# SAM_E54_Xplained_Pro_current_measurement.net
KiCad netlist of a schematic drawn in Altium Designer
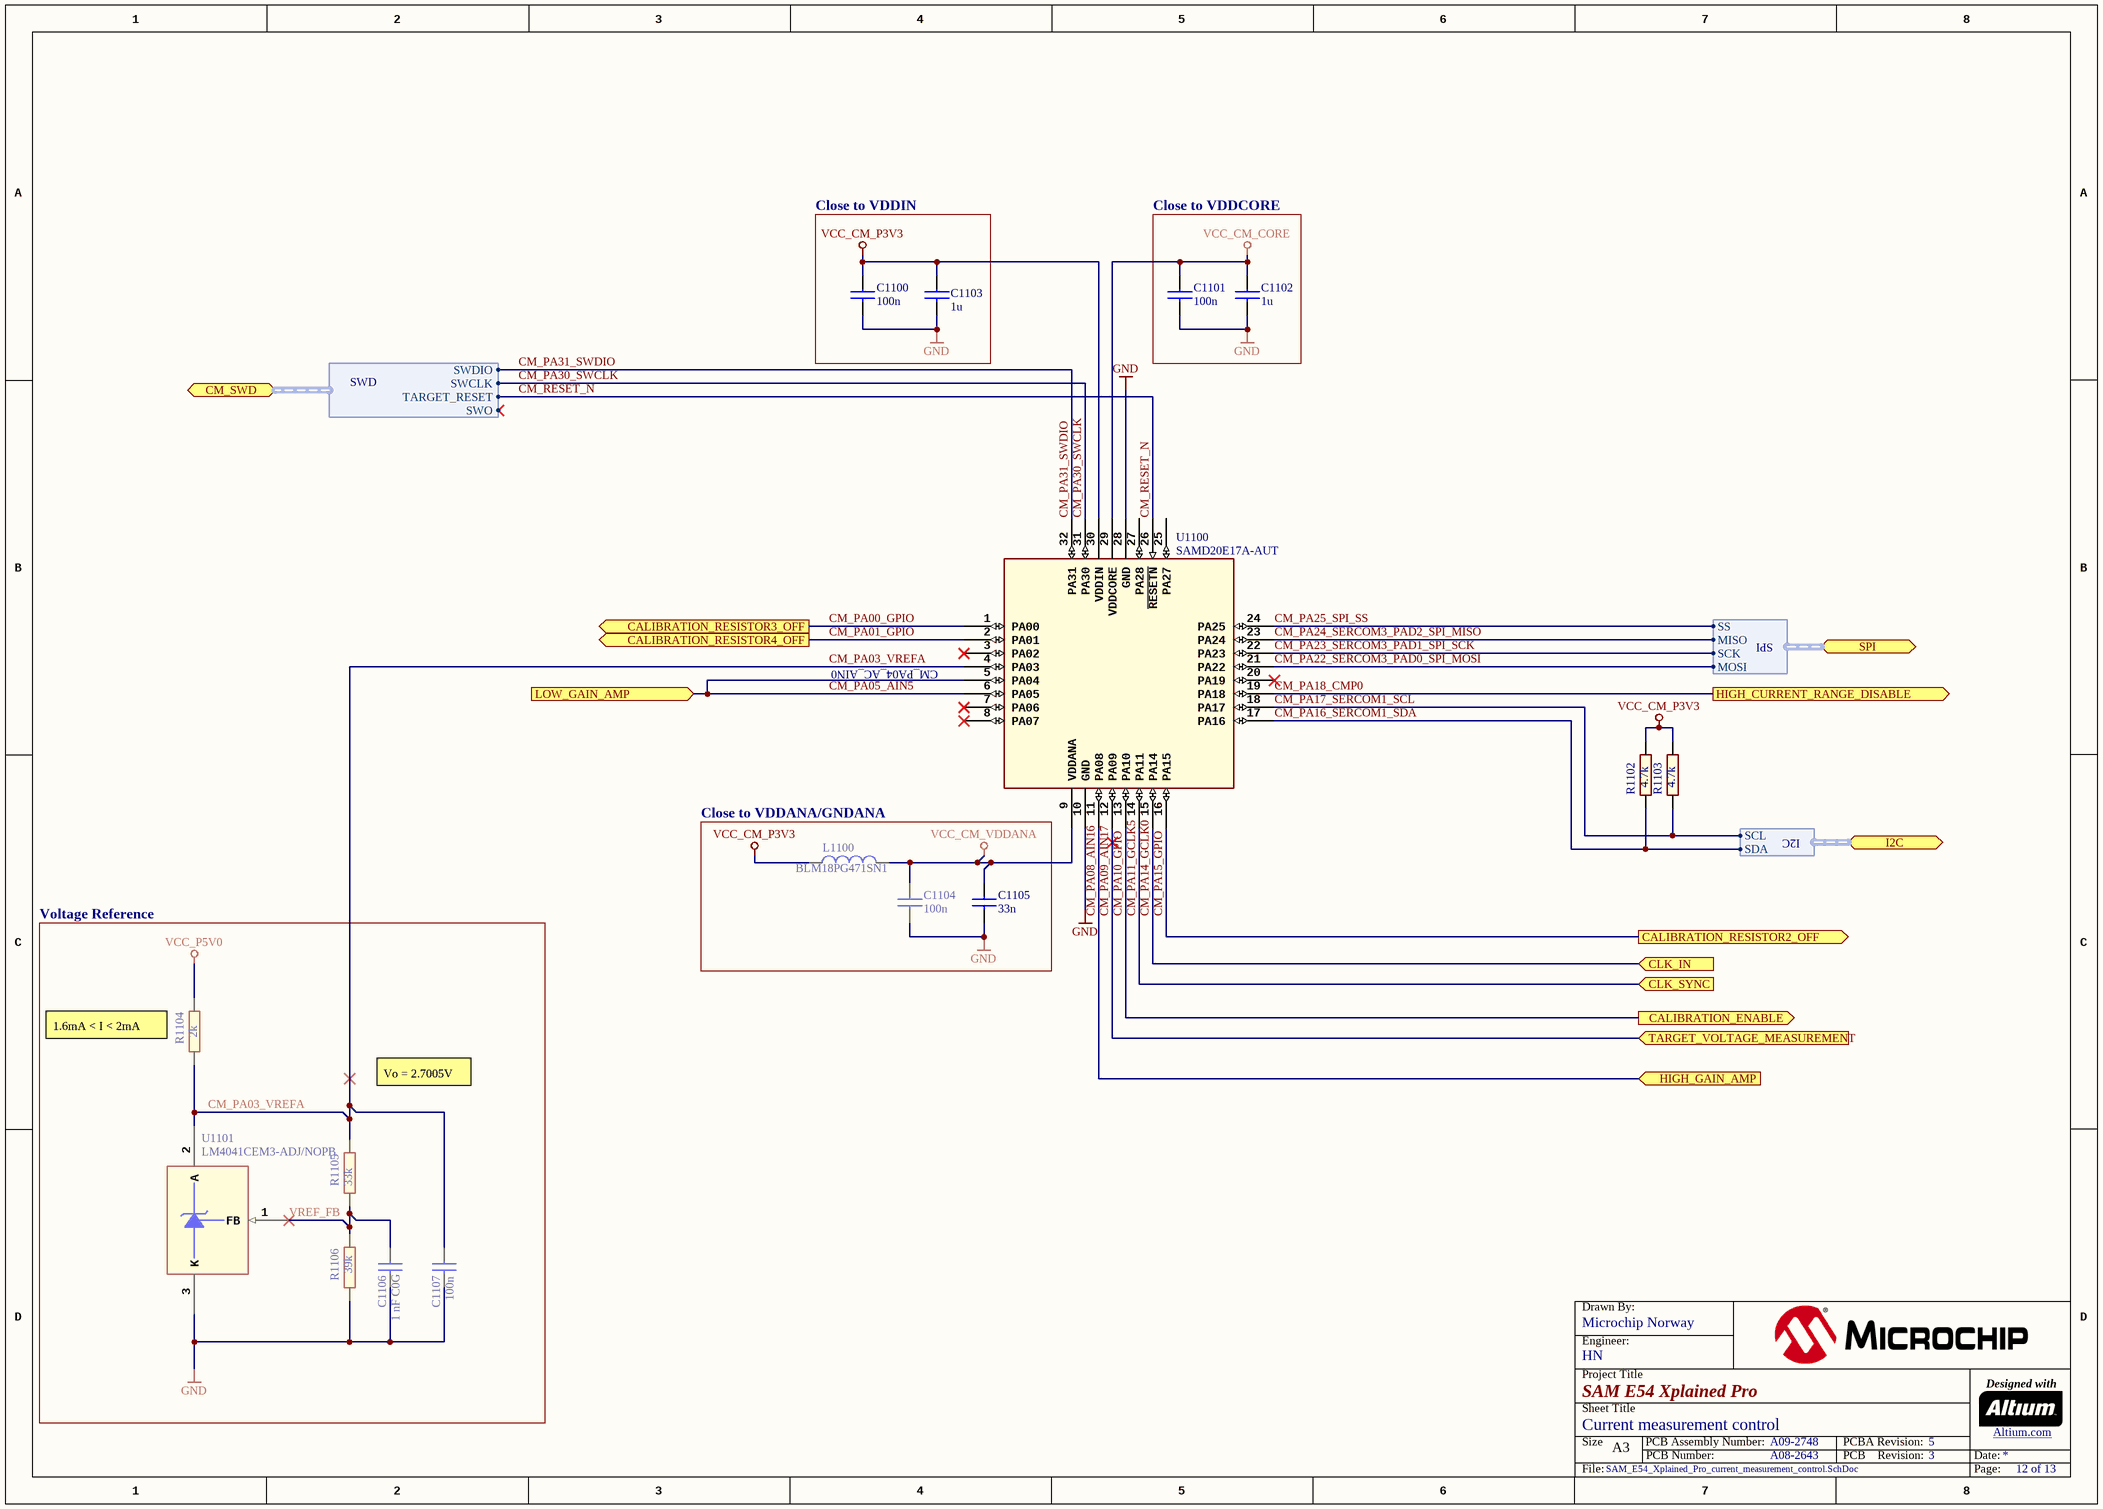
[diagram p0: SAM_E54_Xplained_Pro_current_measurement_control.SchDoc]

(export (version "E")
  (design (tool "Eeschema 10.0.6"))
  (components
    (comp (ref "C1100")
      (value "100n")
      (footprint "AP1-00053")
      (description "Ceramic capacitor, SMD 0402, X7R, 16V, +/-10%")
      (fields (field (name "TOLERANCE") "16V, +/-10%") (field (name "MANUFACTURER") "Kemet"))
      (libsource (lib "AltiumDbLib") (part "CAP-NONPOL"))
    )
    (comp (ref "C1101")
      (value "100n")
      (footprint "AP1-00053")
      (description "Ceramic capacitor, SMD 0402, X7R, 16V, +/-10%")
      (fields (field (name "TOLERANCE") "16V, +/-10%") (field (name "MANUFACTURER") "Kemet"))
      (libsource (lib "AltiumDbLib") (part "CAP-NONPOL"))
    )
    (comp (ref "C1102")
      (value "1u")
      (footprint "AP1-00053")
      (description "Ceramic capacitor, SMD 0402, X5R, 6.3V, +/-10% (de26942)")
      (fields (field (name "TOLERANCE") "+/-10%") (field (name "MANUFACTURER") "Kemet"))
      (libsource (lib "AltiumDbLib") (part "CAP-NONPOL"))
    )
    (comp (ref "C1103")
      (value "1u")
      (footprint "AP1-00053")
      (description "Ceramic capacitor, SMD 0402, X5R, 6.3V, +/-10% (de26942)")
      (fields (field (name "TOLERANCE") "+/-10%") (field (name "MANUFACTURER") "Kemet"))
      (libsource (lib "AltiumDbLib") (part "CAP-NONPOL"))
    )
    (comp (ref "C1104")
      (value "100n")
      (footprint "AP1-00053")
      (description "Ceramic capacitor, SMD 0402, X7R, 16V, +/-10%")
      (fields (field (name "TOLERANCE") "16V, +/-10%") (field (name "MANUFACTURER") "Kemet"))
      (libsource (lib "AltiumDbLib") (part "CAP-NONPOL"))
    )
    (comp (ref "C1105")
      (value "33n")
      (footprint "AP1-00053")
      (description "Ceramic capacitor, SMD 0402, X7R, 25V, ±10%")
      (fields (field (name "TOLERANCE") "±10%(K)") (field (name "MANUFACTURER") "Murata"))
      (libsource (lib "AltiumDbLib") (part "CAP-NONPOL"))
    )
    (comp (ref "C1106")
      (value "1 nF C0G")
      (footprint "AP1-00053")
      (description "Ceramic capacitor, SMD 0402, C0G, 50V, +/-5%")
      (fields (field (name "TOLERANCE") "5%") (field (name "MANUFACTURER") "Murata"))
      (libsource (lib "AltiumDbLib") (part "CAP-NONPOL"))
    )
    (comp (ref "C1107")
      (value "100n")
      (footprint "AP1-00053")
      (description "Ceramic capacitor, SMD 0402, X7R, 16V, +/-10%")
      (fields (field (name "TOLERANCE") "16V, +/-10%") (field (name "MANUFACTURER") "Kemet"))
      (libsource (lib "AltiumDbLib") (part "CAP-NONPOL"))
    )
    (comp (ref "L1100")
      (value "BLM18PG471SN1")
      (footprint "AP3-00005")
      (description "SMD RF inductor 0603. Z=470Ohm (@100MHz), Max R(dc)=0.65Ohm, Max current=1A")
      (fields (field (name "MANUFACTURER") "Murata"))
      (libsource (lib "AltiumDbLib") (part "INDUCTOR"))
    )
    (comp (ref "R1102")
      (value "4.7k")
      (footprint "AP2-00011")
      (description "Thick film resistor, SMD 0402, 1/16W, 1%")
      (fields (field (name "TOLERANCE") "1 %") (field (name "MANUFACTURER") "PHYCOMP"))
      (libsource (lib "") (part "R2_1"))
    )
    (comp (ref "R1103")
      (value "4.7k")
      (footprint "AP2-00011")
      (description "Thick film resistor, SMD 0402, 1/16W, 1%")
      (fields (field (name "TOLERANCE") "1 %") (field (name "MANUFACTURER") "PHYCOMP"))
      (libsource (lib "") (part "R2_1"))
    )
    (comp (ref "R1104")
      (value "2k")
      (footprint "AP2-00011")
      (description "Thick film resistor, SMD 0402, 1/16W, 1%")
      (fields (field (name "TOLERANCE") "1 %"))
      (libsource (lib "AltiumDbLib") (part "R2"))
    )
    (comp (ref "R1105")
      (value "33k")
      (footprint "AP2-00011")
      (description "Thick film resistor, SMD 0402, 1/16W, 1%")
      (fields (field (name "TOLERANCE") "1 %") (field (name "MANUFACTURER") "ASJ"))
      (libsource (lib "AltiumDbLib") (part "R2"))
    )
    (comp (ref "R1106")
      (value "39k")
      (footprint "AP2-00011")
      (description "Thick film resistor, SMD 0402, 1/16W, 1%")
      (fields (field (name "TOLERANCE") "1 %") (field (name "MANUFACTURER") "ASJ"))
      (libsource (lib "AltiumDbLib") (part "R2"))
    )
    (comp (ref "U1100")
      (value "SAMD20E17A-AUT")
      (footprint "AP6-00061")
      (description "Atmel 32bit RISC MCU 32 pin")
      (fields (field (name "MANUFACTURER") "ATMEL") (field (name "MPN") "ATSAMD20E17A-AUT"))
      (libsource (lib "AltiumDbLib") (part "SAMD20E"))
    )
    (comp (ref "U1101")
      (value "LM4041CEM3-ADJ/NOPB")
      (footprint "AP5-00002")
      (description "Adjustable shunt voltage regulator, 1.24 to 10V out")
      (fields (field (name "MANUFACTURER") "Texas Instruments"))
      (libsource (lib "AltiumDbLib") (part "LM4041-ADJ"))
    )
  )
  (nets
    (net (code "4") (name "/CM_PA00_GPIO") (class "Default")
      (node (ref "U1100") (pin "1") (pinfunction "PA00_1") (pintype "bidirectional"))
    )
    (net (code "5") (name "/CM_PA01_GPIO") (class "Default")
      (node (ref "U1100") (pin "2") (pinfunction "PA01_2") (pintype "bidirectional"))
    )
    (net (code "6") (name "/CM_PA03_VREFA") (class "Default")
      (node (ref "C1107") (pin "1") (pinfunction "1_1") (pintype "passive"))
      (node (ref "R1104") (pin "1") (pinfunction "1_1") (pintype "passive"))
      (node (ref "R1105") (pin "2") (pinfunction "2_2") (pintype "passive"))
      (node (ref "U1100") (pin "4") (pinfunction "PA03_4") (pintype "bidirectional"))
      (node (ref "U1101") (pin "2") (pinfunction "A_2") (pintype "power_in"))
    )
    (net (code "7") (name "/CM_PA05_AIN5") (class "Default")
      (node (ref "U1100") (pin "5") (pinfunction "PA04_5") (pintype "bidirectional"))
      (node (ref "U1100") (pin "6") (pinfunction "PA05_6") (pintype "bidirectional"))
    )
    (net (code "8") (name "/CM_PA08_AIN16") (class "Default")
      (node (ref "U1100") (pin "11") (pinfunction "PA08_11") (pintype "bidirectional"))
    )
    (net (code "9") (name "/CM_PA09_AIN17") (class "Default")
      (node (ref "U1100") (pin "12") (pinfunction "PA09_12") (pintype "bidirectional"))
    )
    (net (code "10") (name "/CM_PA10_GPIO") (class "Default")
      (node (ref "U1100") (pin "13") (pinfunction "PA10_13") (pintype "bidirectional"))
    )
    (net (code "11") (name "/CM_PA11_GCLK5") (class "Default")
      (node (ref "U1100") (pin "14") (pinfunction "PA11_14") (pintype "bidirectional"))
    )
    (net (code "12") (name "/CM_PA14_GCLK0") (class "Default")
      (node (ref "U1100") (pin "15") (pinfunction "PA14_15") (pintype "bidirectional"))
    )
    (net (code "13") (name "/CM_PA15_GPIO") (class "Default")
      (node (ref "U1100") (pin "16") (pinfunction "PA15_16") (pintype "bidirectional"))
    )
    (net (code "14") (name "/CM_PA16_SERCOM1_SDA") (class "Default")
      (node (ref "R1102") (pin "1") (pinfunction "1_1") (pintype "passive"))
      (node (ref "U1100") (pin "17") (pinfunction "PA16_17") (pintype "bidirectional"))
    )
    (net (code "15") (name "/CM_PA17_SERCOM1_SCL") (class "Default")
      (node (ref "R1103") (pin "1") (pinfunction "1_1") (pintype "passive"))
      (node (ref "U1100") (pin "18") (pinfunction "PA17_18") (pintype "bidirectional"))
    )
    (net (code "16") (name "/CM_PA18_CMP0") (class "Default")
      (node (ref "U1100") (pin "19") (pinfunction "PA18_19") (pintype "bidirectional"))
    )
    (net (code "17") (name "/CM_PA22_SERCOM3_PAD0_SPI_MOSI") (class "Default")
      (node (ref "U1100") (pin "21") (pinfunction "PA22_21") (pintype "bidirectional"))
    )
    (net (code "18") (name "/CM_PA23_SERCOM3_PAD1_SPI_SCK") (class "Default")
      (node (ref "U1100") (pin "22") (pinfunction "PA23_22") (pintype "bidirectional"))
    )
    (net (code "19") (name "/CM_PA24_SERCOM3_PAD2_SPI_MISO") (class "Default")
      (node (ref "U1100") (pin "23") (pinfunction "PA24_23") (pintype "bidirectional"))
    )
    (net (code "20") (name "/CM_PA25_SPI_SS") (class "Default")
      (node (ref "U1100") (pin "24") (pinfunction "PA25_24") (pintype "bidirectional"))
    )
    (net (code "21") (name "/CM_PA30_SWCLK") (class "Default")
      (node (ref "U1100") (pin "31") (pinfunction "PA30_31") (pintype "bidirectional"))
    )
    (net (code "22") (name "/CM_PA31_SWDIO") (class "Default")
      (node (ref "U1100") (pin "32") (pinfunction "PA31_32") (pintype "bidirectional"))
    )
    (net (code "23") (name "/CM_RESET_N") (class "Default")
      (node (ref "U1100") (pin "26") (pinfunction "~{RESETN}_26") (pintype "input"))
    )
    (net (code "24") (name "/VREF_FB") (class "Default")
      (node (ref "C1106") (pin "1") (pinfunction "1_1") (pintype "passive"))
      (node (ref "R1105") (pin "1") (pinfunction "1_1") (pintype "passive"))
      (node (ref "R1106") (pin "2") (pinfunction "2_2") (pintype "passive"))
      (node (ref "U1101") (pin "1") (pinfunction "FB_1") (pintype "input"))
    )
    (net (code "28") (name "GND") (class "Default")
      (node (ref "C1100") (pin "2") (pinfunction "2_2") (pintype "passive"))
      (node (ref "C1101") (pin "2") (pinfunction "2_2") (pintype "passive"))
      (node (ref "C1102") (pin "2") (pinfunction "2_2") (pintype "passive"))
      (node (ref "C1103") (pin "2") (pinfunction "2_2") (pintype "passive"))
      (node (ref "C1104") (pin "2") (pinfunction "2_2") (pintype "passive"))
      (node (ref "C1105") (pin "2") (pinfunction "2_2") (pintype "passive"))
      (node (ref "C1106") (pin "2") (pinfunction "2_2") (pintype "passive"))
      (node (ref "C1107") (pin "2") (pinfunction "2_2") (pintype "passive"))
      (node (ref "R1106") (pin "1") (pinfunction "1_1") (pintype "passive"))
      (node (ref "U1100") (pin "10") (pinfunction "GND_10") (pintype "power_in"))
      (node (ref "U1100") (pin "28") (pinfunction "GND_28") (pintype "power_in"))
      (node (ref "U1101") (pin "3") (pinfunction "K_3") (pintype "power_in"))
    )
    (net (code "29") (name "VCC_CM_CORE") (class "Default")
      (node (ref "C1101") (pin "1") (pinfunction "1_1") (pintype "passive"))
      (node (ref "C1102") (pin "1") (pinfunction "1_1") (pintype "passive"))
      (node (ref "U1100") (pin "29") (pinfunction "VDDCORE_29") (pintype "power_in"))
    )
    (net (code "30") (name "VCC_CM_P3V3") (class "Default")
      (node (ref "C1100") (pin "1") (pinfunction "1_1") (pintype "passive"))
      (node (ref "C1103") (pin "1") (pinfunction "1_1") (pintype "passive"))
      (node (ref "L1100") (pin "1") (pinfunction "1_1") (pintype "passive"))
      (node (ref "R1102") (pin "2") (pinfunction "2_2") (pintype "passive"))
      (node (ref "R1103") (pin "2") (pinfunction "2_2") (pintype "passive"))
      (node (ref "U1100") (pin "30") (pinfunction "VDDIN_30") (pintype "power_in"))
    )
    (net (code "31") (name "VCC_CM_VDDANA") (class "Default")
      (node (ref "C1104") (pin "1") (pinfunction "1_1") (pintype "passive"))
      (node (ref "C1105") (pin "1") (pinfunction "1_1") (pintype "passive"))
      (node (ref "L1100") (pin "2") (pinfunction "2_2") (pintype "passive"))
      (node (ref "U1100") (pin "9") (pinfunction "VDDANA_9") (pintype "power_in"))
    )
    (net (code "32") (name "VCC_P5V0") (class "Default")
      (node (ref "R1104") (pin "2") (pinfunction "2_2") (pintype "passive"))
    )
    (net (code "33") (name "unconnected-(U1100-PA02-Pad3)") (class "Default")
      (node (ref "U1100") (pin "3") (pinfunction "PA02_3") (pintype "bidirectional+no_connect"))
    )
    (net (code "34") (name "unconnected-(U1100-PA06-Pad7)") (class "Default")
      (node (ref "U1100") (pin "7") (pinfunction "PA06_7") (pintype "bidirectional+no_connect"))
    )
    (net (code "35") (name "unconnected-(U1100-PA07-Pad8)") (class "Default")
      (node (ref "U1100") (pin "8") (pinfunction "PA07_8") (pintype "bidirectional+no_connect"))
    )
    (net (code "36") (name "unconnected-(U1100-PA19-Pad20)") (class "Default")
      (node (ref "U1100") (pin "20") (pinfunction "PA19_20") (pintype "bidirectional+no_connect"))
    )
    (net (code "37") (name "unconnected-(U1100-PA27-Pad25)") (class "Default")
      (node (ref "U1100") (pin "25") (pinfunction "PA27_25") (pintype "bidirectional"))
    )
    (net (code "38") (name "unconnected-(U1100-PA28-Pad27)") (class "Default")
      (node (ref "U1100") (pin "27") (pinfunction "PA28_27") (pintype "bidirectional"))
    )
  )
)
